# communicator_v2p3.net
KiCad netlist of a schematic drawn in EAGLE
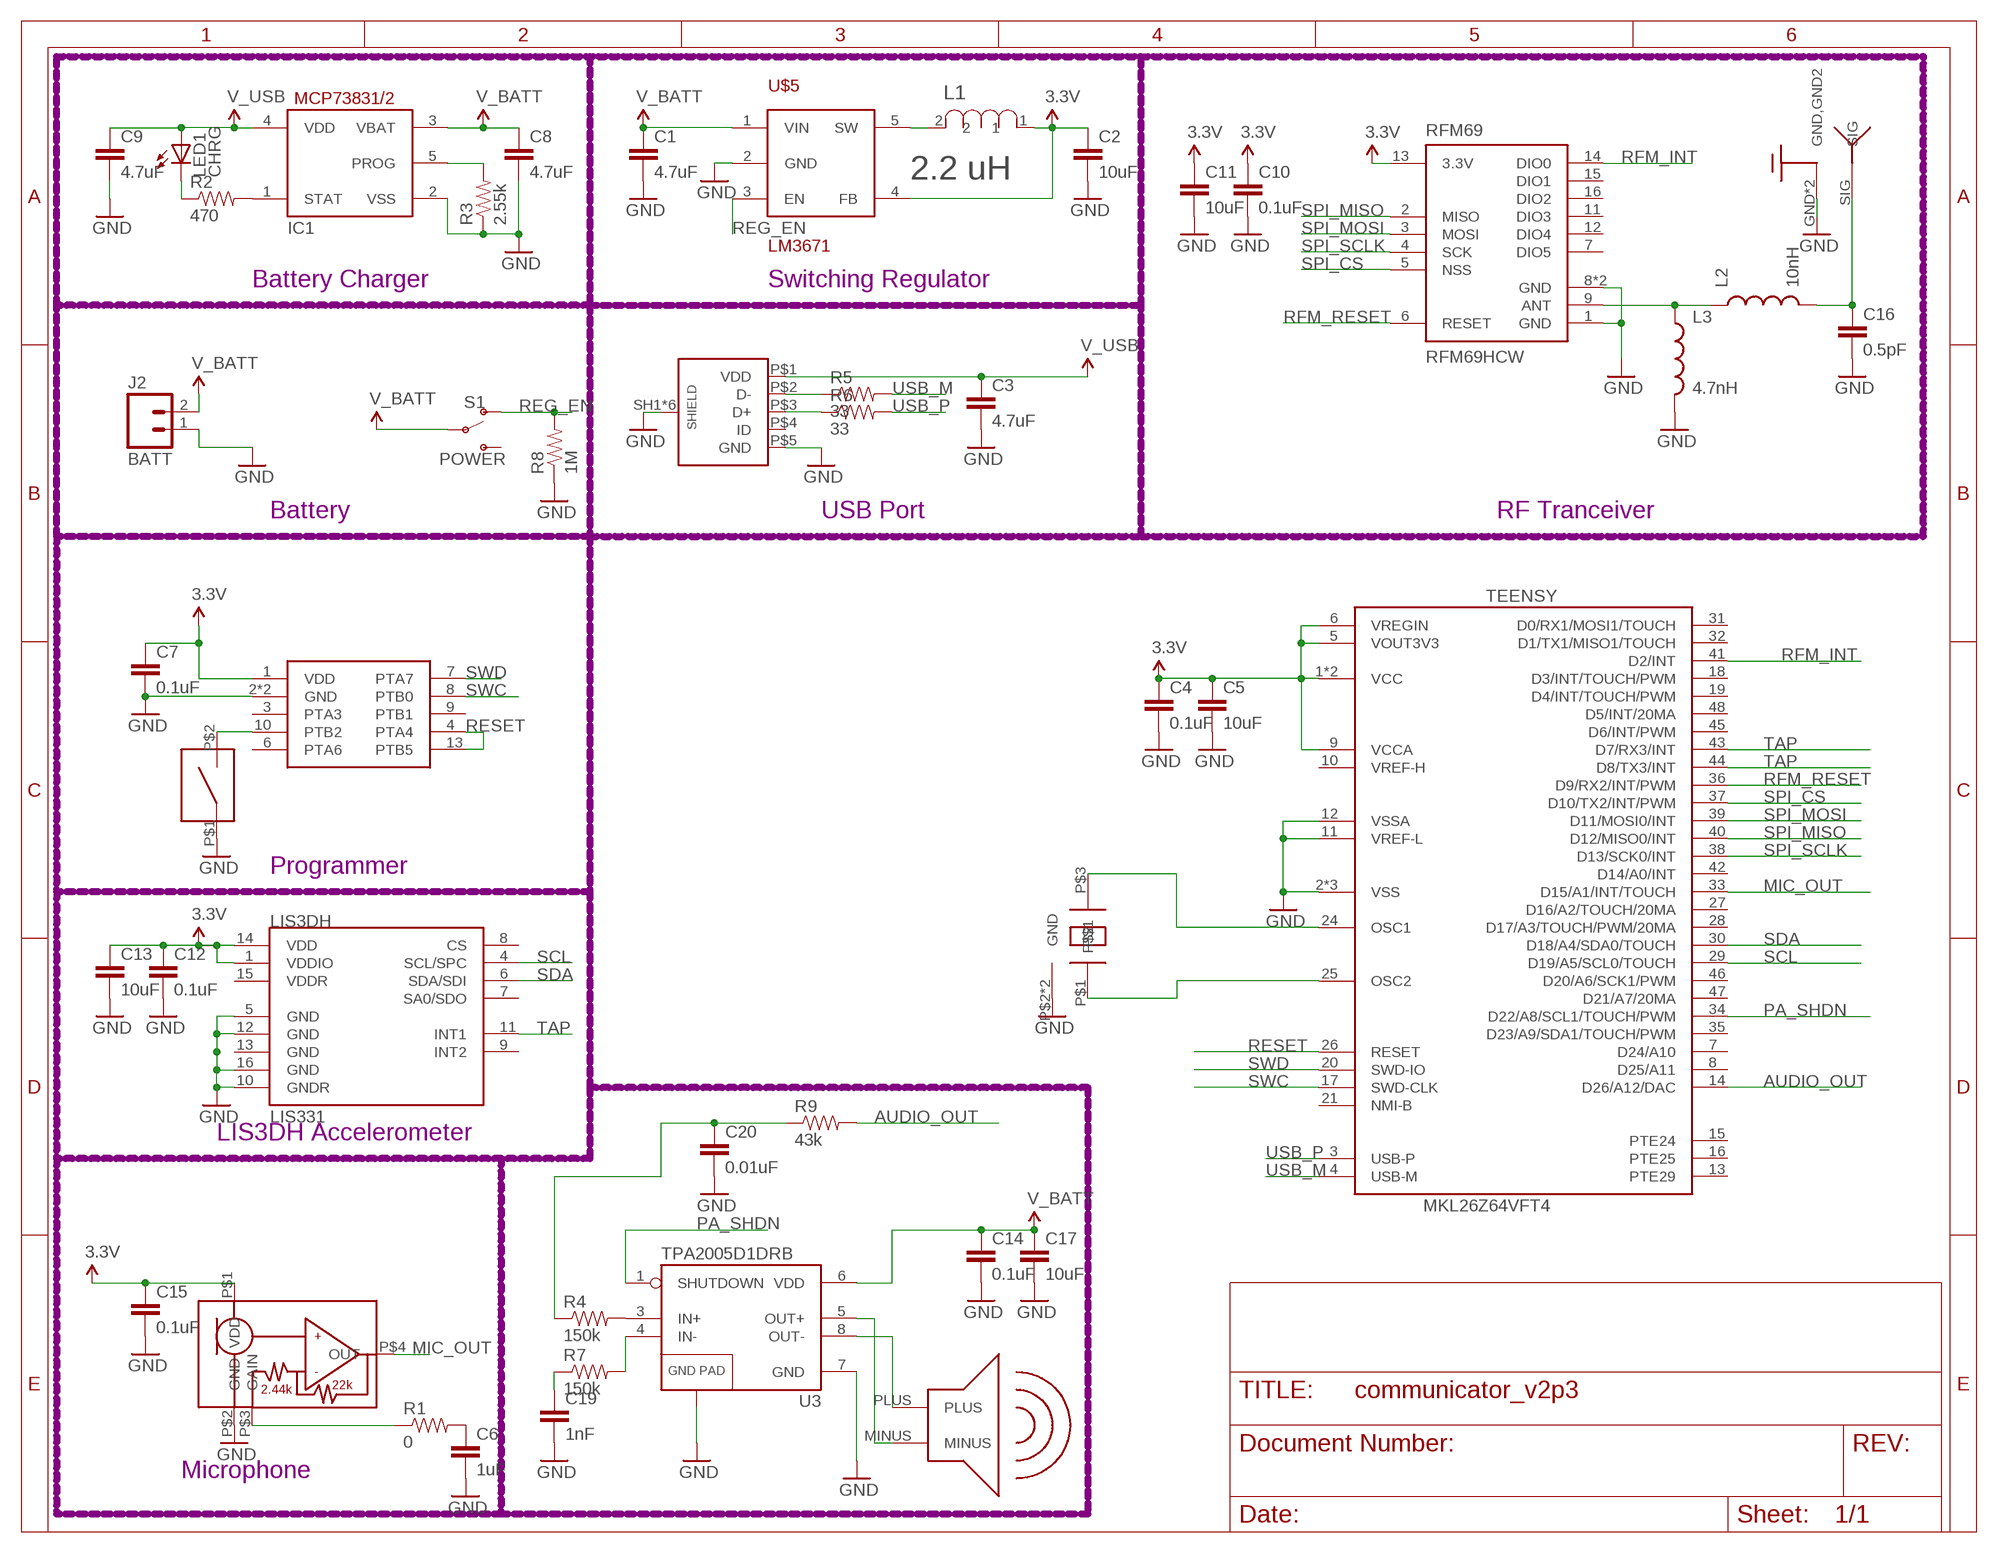
[diagram p0: schematic, sheet 1]

(export (version "E")
  (design (tool "Eeschema 10.0.6"))
  (components
    (comp (ref "3X3MM1")
      (value "CURRENT_BOOTLOADER3X3MM")
      (footprint "eagle-import:QFN50P300X300X100-17N")
      (libsource (lib "eagle-import") (part "CURRENT_BOOTLOADER3X3MM"))
    )
    (comp (ref "C1")
      (value "4.7uF")
      (footprint "eagle-import:0603-CAP")
      (libsource (lib "eagle-import") (part "0.1UF-25V(+80/-20%)(0603)"))
    )
    (comp (ref "C2")
      (value "10uF")
      (footprint "eagle-import:0603-CAP")
      (libsource (lib "eagle-import") (part "2.2UF-10V-20%(0603)"))
    )
    (comp (ref "C3")
      (value "4.7uF")
      (footprint "eagle-import:0603-CAP")
      (libsource (lib "eagle-import") (part "2.2UF-10V-20%(0603)"))
    )
    (comp (ref "C4")
      (value "0.1uF")
      (footprint "eagle-import:0603-CAP")
      (libsource (lib "eagle-import") (part "0.1UF-25V(+80/-20%)(0603)"))
    )
    (comp (ref "C5")
      (value "10uF")
      (footprint "eagle-import:0603-CAP")
      (libsource (lib "eagle-import") (part "10UF-6.3V-20%(0603)"))
    )
    (comp (ref "C6")
      (value "1uF")
      (footprint "eagle-import:0603-CAP")
      (libsource (lib "eagle-import") (part "0.1UF-25V(+80/-20%)(0603)"))
    )
    (comp (ref "C7")
      (value "0.1uF")
      (footprint "eagle-import:0603-CAP")
      (libsource (lib "eagle-import") (part "0.1UF-25V(+80/-20%)(0603)"))
    )
    (comp (ref "C8")
      (value "4.7uF")
      (footprint "eagle-import:0603-CAP")
      (libsource (lib "eagle-import") (part "4.7UF-6.3V-10%(0603)0603"))
    )
    (comp (ref "C9")
      (value "4.7uF")
      (footprint "eagle-import:0603-CAP")
      (libsource (lib "eagle-import") (part "4.7UF-6.3V-10%(0603)0603"))
    )
    (comp (ref "C10")
      (value "0.1uF")
      (footprint "eagle-import:0603-CAP")
      (libsource (lib "eagle-import") (part "0.1UF-25V(+80/-20%)(0603)"))
    )
    (comp (ref "C11")
      (value "10uF")
      (footprint "eagle-import:0603-CAP")
      (libsource (lib "eagle-import") (part "10UF-6.3V-20%(0603)"))
    )
    (comp (ref "C12")
      (value "0.1uF")
      (footprint "eagle-import:0603-CAP")
      (libsource (lib "eagle-import") (part "0.1UF-25V(+80/-20%)(0603)"))
    )
    (comp (ref "C13")
      (value "10uF")
      (footprint "eagle-import:0603-CAP")
      (libsource (lib "eagle-import") (part "10UF-6.3V-20%(0603)"))
    )
    (comp (ref "C14")
      (value "0.1uF")
      (footprint "eagle-import:0603-CAP")
      (libsource (lib "eagle-import") (part "0.1UF-25V(+80/-20%)(0603)"))
    )
    (comp (ref "C15")
      (value "0.1uF")
      (footprint "eagle-import:0603-CAP")
      (libsource (lib "eagle-import") (part "0.1UF-25V(+80/-20%)(0603)"))
    )
    (comp (ref "C16")
      (value "0.5pF")
      (footprint "eagle-import:0603-CAP")
      (libsource (lib "eagle-import") (part "0.75PF-50V(-/+.25PF)(0603)"))
    )
    (comp (ref "C17")
      (value "10uF")
      (footprint "eagle-import:0603-CAP")
      (libsource (lib "eagle-import") (part "10UF-6.3V-20%(0603)"))
    )
    (comp (ref "C19")
      (value "1nF")
      (footprint "eagle-import:0603-CAP")
      (libsource (lib "eagle-import") (part "0.1UF-25V(+80/-20%)(0603)"))
    )
    (comp (ref "C20")
      (value "0.01uF")
      (footprint "eagle-import:0603-CAP")
      (libsource (lib "eagle-import") (part "0.1UF-25V(+80/-20%)(0603)"))
    )
    (comp (ref "IC1")
      (value "MCP73831/OT")
      (footprint "eagle-import:SOT23-5L")
      (libsource (lib "eagle-import") (part "MCP73831/OT"))
    )
    (comp (ref "J2")
      (value "BATT")
      (footprint "eagle-import:1X02")
      (libsource (lib "eagle-import") (part "M02PTH"))
    )
    (comp (ref "L1")
      (value "2.2 uH")
      (footprint "eagle-import:INDC3225X22N")
      (fields (field (name "MPN") "PM1210-2R2J-RC") (field (name "TOLERANCE") "±5 %"))
      (libsource (lib "eagle-import") (part "PM1210-2R2J-RC"))
    )
    (comp (ref "L2")
      (value "10nH")
      (footprint "eagle-import:0603")
      (libsource (lib "eagle-import") (part "INDUCTOR0603"))
    )
    (comp (ref "L3")
      (value "4.7nH")
      (footprint "eagle-import:0603")
      (libsource (lib "eagle-import") (part "INDUCTOR0603"))
    )
    (comp (ref "LED1")
      (value "CHRG")
      (footprint "eagle-import:CHIPLED_0805")
      (libsource (lib "eagle-import") (part "LEDCHIPLED_0805"))
    )
    (comp (ref "LIS3DH")
      (value "LIS331")
      (footprint "eagle-import:LGA16-3MM")
      (libsource (lib "eagle-import") (part "LIS331"))
    )
    (comp (ref "R1")
      (value "0")
      (footprint "eagle-import:0603-RES")
      (libsource (lib "eagle-import") (part "33OHM1/10W1%(0603)"))
    )
    (comp (ref "R2")
      (value "470")
      (footprint "eagle-import:0603-RES")
      (libsource (lib "eagle-import") (part "470OHM1/10W1%(0603)"))
    )
    (comp (ref "R3")
      (value "2.55k")
      (footprint "eagle-import:0603-RES")
      (libsource (lib "eagle-import") (part "2.55KOHM-1/10W-1%(0603)"))
    )
    (comp (ref "R4")
      (value "150k")
      (footprint "eagle-import:0603-RES")
      (libsource (lib "eagle-import") (part "33OHM1/10W1%(0603)"))
    )
    (comp (ref "R5")
      (value "33")
      (footprint "eagle-import:0603-RES")
      (libsource (lib "eagle-import") (part "33OHM1/10W1%(0603)"))
    )
    (comp (ref "R6")
      (value "33")
      (footprint "eagle-import:0603-RES")
      (libsource (lib "eagle-import") (part "33OHM1/10W1%(0603)"))
    )
    (comp (ref "R7")
      (value "150k")
      (footprint "eagle-import:0603-RES")
      (libsource (lib "eagle-import") (part "33OHM1/10W1%(0603)"))
    )
    (comp (ref "R8")
      (value "1M")
      (footprint "eagle-import:0603-RES")
      (libsource (lib "eagle-import") (part "2.55KOHM-1/10W-1%(0603)"))
    )
    (comp (ref "R9")
      (value "43k")
      (footprint "eagle-import:0603-RES")
      (libsource (lib "eagle-import") (part "33OHM1/10W1%(0603)"))
    )
    (comp (ref "RFM69")
      (value "RFM69HCW")
      (footprint "eagle-import:RFM69HCW-XXXS2")
      (libsource (lib "eagle-import") (part "RFM69HCW"))
    )
    (comp (ref "S1")
      (value "POWER")
      (footprint "eagle-import:SWITCH_SPST_SMD_A")
      (libsource (lib "eagle-import") (part "SWITCH-SPDT-SMD-RIGHT-ANGLE"))
    )
    (comp (ref "TEENSY")
      (value "MKL26Z64VFT4")
      (footprint "eagle-import:QFN50P700X700X100-49N")
      (libsource (lib "eagle-import") (part "MKL26Z64VFT4"))
    )
    (comp (ref "U$1")
      (value "ANTENNA_915MHZ")
      (footprint "eagle-import:ANTENNA_915MHZ")
      (libsource (lib "eagle-import") (part "ANTENNA_915MHZ"))
    )
    (comp (ref "U$2")
      (value "MICROPHONE")
      (footprint "eagle-import:SPU0414HR5H-SB")
      (libsource (lib "eagle-import") (part "MICROPHONE"))
    )
    (comp (ref "U$3")
      (value "SPEAKER")
      (footprint "eagle-import:PSR1511N08S3K")
      (libsource (lib "eagle-import") (part "SPEAKER"))
    )
    (comp (ref "U$4")
      (value "KXT131LHS")
      (footprint "eagle-import:KXT131LHS")
      (libsource (lib "eagle-import") (part "KXT131LHS"))
    )
    (comp (ref "U$5")
      (value "LM3671")
      (footprint "eagle-import:SOT23-5")
      (libsource (lib "eagle-import") (part "LM3671"))
    )
    (comp (ref "U$8")
      (value "MICRO_USB_B")
      (footprint "eagle-import:MICRO_USB_B")
      (libsource (lib "eagle-import") (part "MICRO_USB_B"))
    )
    (comp (ref "U$9")
      (value "TSX-3225")
      (footprint "eagle-import:TSX-3225")
      (libsource (lib "eagle-import") (part "TSX-3225"))
    )
    (comp (ref "U3")
      (value "TPA2005D1DRB")
      (footprint "eagle-import:QFN-8_PAD")
      (libsource (lib "eagle-import") (part "TPA2005D1DRB"))
    )
  )
  (nets
    (net (code "1") (name "/AUDIO_OUT") (class "Default")
      (node (ref "R9") (pin "2") (pinfunction "2_2") (pintype "passive"))
      (node (ref "TEENSY") (pin "14") (pinfunction "D26/A12/DAC_14") (pintype "bidirectional"))
    )
    (net (code "2") (name "/MIC_OUT") (class "Default")
      (node (ref "TEENSY") (pin "33") (pinfunction "D15/A1/INT/TOUCH_33") (pintype "bidirectional"))
      (node (ref "U$2") (pin "P$4") (pinfunction "OUT_P$4") (pintype "bidirectional"))
    )
    (net (code "3") (name "/PA_SHDN") (class "Default")
      (node (ref "TEENSY") (pin "34") (pinfunction "D22/A8/SCL1/TOUCH/PWM_34") (pintype "bidirectional"))
      (node (ref "U3") (pin "1") (pinfunction "SHUTDOWN_1") (pintype "input"))
    )
    (net (code "4") (name "/REG_EN") (class "Default")
      (node (ref "R8") (pin "2") (pinfunction "2_2") (pintype "passive"))
      (node (ref "S1") (pin "1") (pinfunction "O_1") (pintype "passive"))
      (node (ref "U$5") (pin "3") (pinfunction "EN_3") (pintype "bidirectional"))
    )
    (net (code "5") (name "/RESET") (class "Default")
      (node (ref "3X3MM1") (pin "13") (pinfunction "PTB5_13") (pintype "bidirectional"))
      (node (ref "3X3MM1") (pin "4") (pinfunction "PTA4_4") (pintype "bidirectional"))
      (node (ref "TEENSY") (pin "26") (pinfunction "RESET_26") (pintype "bidirectional"))
    )
    (net (code "6") (name "/RFM_INT") (class "Default")
      (node (ref "RFM69") (pin "14") (pinfunction "DIO0_14") (pintype "bidirectional"))
      (node (ref "TEENSY") (pin "41") (pinfunction "D2/INT_41") (pintype "bidirectional"))
    )
    (net (code "7") (name "/RFM_RESET") (class "Default")
      (node (ref "RFM69") (pin "6") (pinfunction "RESET_6") (pintype "input"))
      (node (ref "TEENSY") (pin "36") (pinfunction "D9/RX2/INT/PWM_36") (pintype "bidirectional"))
    )
    (net (code "8") (name "/SCL") (class "Default")
      (node (ref "LIS3DH") (pin "4") (pinfunction "SCL/SPC_4") (pintype "bidirectional"))
      (node (ref "TEENSY") (pin "29") (pinfunction "D19/A5/SCL0/TOUCH_29") (pintype "bidirectional"))
    )
    (net (code "9") (name "/SDA") (class "Default")
      (node (ref "LIS3DH") (pin "6") (pinfunction "SDA/SDI_6") (pintype "bidirectional"))
      (node (ref "TEENSY") (pin "30") (pinfunction "D18/A4/SDA0/TOUCH_30") (pintype "bidirectional"))
    )
    (net (code "10") (name "/SPI_CS") (class "Default")
      (node (ref "RFM69") (pin "5") (pinfunction "NSS_5") (pintype "input"))
      (node (ref "TEENSY") (pin "37") (pinfunction "D10/TX2/INT/PWM_37") (pintype "bidirectional"))
    )
    (net (code "11") (name "/SPI_MISO") (class "Default")
      (node (ref "RFM69") (pin "2") (pinfunction "MISO_2") (pintype "bidirectional"))
      (node (ref "TEENSY") (pin "40") (pinfunction "D12/MISO0/INT_40") (pintype "bidirectional"))
    )
    (net (code "12") (name "/SPI_MOSI") (class "Default")
      (node (ref "RFM69") (pin "3") (pinfunction "MOSI_3") (pintype "input"))
      (node (ref "TEENSY") (pin "39") (pinfunction "D11/MOSI0/INT_39") (pintype "bidirectional"))
    )
    (net (code "13") (name "/SPI_SCLK") (class "Default")
      (node (ref "RFM69") (pin "4") (pinfunction "SCK_4") (pintype "input"))
      (node (ref "TEENSY") (pin "38") (pinfunction "D13/SCK0/INT_38") (pintype "bidirectional"))
    )
    (net (code "14") (name "/SWC") (class "Default")
      (node (ref "3X3MM1") (pin "8") (pinfunction "PTB0_8") (pintype "bidirectional"))
      (node (ref "TEENSY") (pin "17") (pinfunction "SWD-CLK_17") (pintype "bidirectional"))
    )
    (net (code "15") (name "/SWD") (class "Default")
      (node (ref "3X3MM1") (pin "7") (pinfunction "PTA7_7") (pintype "bidirectional"))
      (node (ref "TEENSY") (pin "20") (pinfunction "SWD-IO_20") (pintype "bidirectional"))
    )
    (net (code "16") (name "/TAP") (class "Default")
      (node (ref "LIS3DH") (pin "11") (pinfunction "INT1_11") (pintype "bidirectional"))
      (node (ref "TEENSY") (pin "43") (pinfunction "D7/RX3/INT_43") (pintype "bidirectional"))
      (node (ref "TEENSY") (pin "44") (pinfunction "D8/TX3/INT_44") (pintype "bidirectional"))
    )
    (net (code "17") (name "/USB_M") (class "Default")
      (node (ref "R5") (pin "2") (pinfunction "2_2") (pintype "passive"))
      (node (ref "TEENSY") (pin "4") (pinfunction "USB-M_4") (pintype "bidirectional"))
    )
    (net (code "18") (name "/USB_P") (class "Default")
      (node (ref "R6") (pin "2") (pinfunction "2_2") (pintype "passive"))
      (node (ref "TEENSY") (pin "3") (pinfunction "USB-P_3") (pintype "bidirectional"))
    )
    (net (code "19") (name "3.3V") (class "Default")
      (node (ref "3X3MM1") (pin "1") (pinfunction "VDD_1") (pintype "bidirectional"))
      (node (ref "C10") (pin "1") (pinfunction "1_1") (pintype "passive"))
      (node (ref "C11") (pin "1") (pinfunction "1_1") (pintype "passive"))
      (node (ref "C12") (pin "1") (pinfunction "1_1") (pintype "passive"))
      (node (ref "C13") (pin "1") (pinfunction "1_1") (pintype "passive"))
      (node (ref "C15") (pin "1") (pinfunction "1_1") (pintype "passive"))
      (node (ref "C2") (pin "1") (pinfunction "1_1") (pintype "passive"))
      (node (ref "C4") (pin "1") (pinfunction "1_1") (pintype "passive"))
      (node (ref "C5") (pin "1") (pinfunction "1_1") (pintype "passive"))
      (node (ref "C7") (pin "1") (pinfunction "1_1") (pintype "passive"))
      (node (ref "L1") (pin "1") (pinfunction "1_1") (pintype "passive"))
      (node (ref "LIS3DH") (pin "1") (pinfunction "VDDIO_1") (pintype "bidirectional"))
      (node (ref "LIS3DH") (pin "14") (pinfunction "VDD_14") (pintype "bidirectional"))
      (node (ref "RFM69") (pin "13") (pinfunction "3.3V_13") (pintype "power_in"))
      (node (ref "TEENSY") (pin "1") (pinfunction "VCC_1") (pintype "bidirectional"))
      (node (ref "TEENSY") (pin "22") (pinfunction "VCC_22") (pintype "bidirectional"))
      (node (ref "TEENSY") (pin "5") (pinfunction "VOUT3V3_5") (pintype "bidirectional"))
      (node (ref "TEENSY") (pin "6") (pinfunction "VREGIN_6") (pintype "bidirectional"))
      (node (ref "TEENSY") (pin "9") (pinfunction "VCCA_9") (pintype "bidirectional"))
      (node (ref "U$2") (pin "P$1") (pinfunction "VDD_P$1") (pintype "bidirectional"))
      (node (ref "U$5") (pin "4") (pinfunction "FB_4") (pintype "bidirectional"))
    )
    (net (code "20") (name "GND") (class "Default")
      (node (ref "3X3MM1") (pin "17") (pinfunction "GND_17") (pintype "bidirectional"))
      (node (ref "3X3MM1") (pin "2") (pinfunction "GND_2") (pintype "bidirectional"))
      (node (ref "C1") (pin "2") (pinfunction "2_2") (pintype "passive"))
      (node (ref "C10") (pin "2") (pinfunction "2_2") (pintype "passive"))
      (node (ref "C11") (pin "2") (pinfunction "2_2") (pintype "passive"))
      (node (ref "C12") (pin "2") (pinfunction "2_2") (pintype "passive"))
      (node (ref "C13") (pin "2") (pinfunction "2_2") (pintype "passive"))
      (node (ref "C14") (pin "2") (pinfunction "2_2") (pintype "passive"))
      (node (ref "C15") (pin "2") (pinfunction "2_2") (pintype "passive"))
      (node (ref "C16") (pin "2") (pinfunction "2_2") (pintype "passive"))
      (node (ref "C17") (pin "2") (pinfunction "2_2") (pintype "passive"))
      (node (ref "C19") (pin "2") (pinfunction "2_2") (pintype "passive"))
      (node (ref "C2") (pin "2") (pinfunction "2_2") (pintype "passive"))
      (node (ref "C20") (pin "2") (pinfunction "2_2") (pintype "passive"))
      (node (ref "C3") (pin "2") (pinfunction "2_2") (pintype "passive"))
      (node (ref "C4") (pin "2") (pinfunction "2_2") (pintype "passive"))
      (node (ref "C5") (pin "2") (pinfunction "2_2") (pintype "passive"))
      (node (ref "C6") (pin "2") (pinfunction "2_2") (pintype "passive"))
      (node (ref "C7") (pin "2") (pinfunction "2_2") (pintype "passive"))
      (node (ref "C8") (pin "2") (pinfunction "2_2") (pintype "passive"))
      (node (ref "C9") (pin "2") (pinfunction "2_2") (pintype "passive"))
      (node (ref "IC1") (pin "2") (pinfunction "VSS_2") (pintype "power_in"))
      (node (ref "J2") (pin "1") (pinfunction "1_1") (pintype "passive"))
      (node (ref "L3") (pin "2") (pinfunction "2_2") (pintype "passive"))
      (node (ref "LIS3DH") (pin "10") (pinfunction "GNDR_10") (pintype "bidirectional"))
      (node (ref "LIS3DH") (pin "12") (pinfunction "GND_12") (pintype "bidirectional"))
      (node (ref "LIS3DH") (pin "16") (pinfunction "GND_16") (pintype "bidirectional"))
      (node (ref "LIS3DH") (pin "5") (pinfunction "GND_5") (pintype "bidirectional"))
      (node (ref "R3") (pin "1") (pinfunction "1_1") (pintype "passive"))
      (node (ref "R8") (pin "1") (pinfunction "1_1") (pintype "passive"))
      (node (ref "RFM69") (pin "1") (pinfunction "GND_1") (pintype "power_in"))
      (node (ref "RFM69") (pin "10") (pinfunction "GND_10") (pintype "power_in"))
      (node (ref "RFM69") (pin "8") (pinfunction "GND_8") (pintype "power_in"))
      (node (ref "TEENSY") (pin "11") (pinfunction "VREF-L_11") (pintype "bidirectional"))
      (node (ref "TEENSY") (pin "12") (pinfunction "VSSA_12") (pintype "bidirectional"))
      (node (ref "TEENSY") (pin "2") (pinfunction "VSS_2") (pintype "bidirectional"))
      (node (ref "TEENSY") (pin "23") (pinfunction "VSS_23") (pintype "bidirectional"))
      (node (ref "TEENSY") (pin "49") (pinfunction "VSS_49") (pintype "bidirectional"))
      (node (ref "U$1") (pin "GND") (pinfunction "GND,GND2_GND") (pintype "bidirectional"))
      (node (ref "U$1") (pin "GND2") (pinfunction "GND,GND2_GND2") (pintype "bidirectional"))
      (node (ref "U$2") (pin "P$2") (pinfunction "GND_P$2") (pintype "bidirectional"))
      (node (ref "U$4") (pin "P$1") (pinfunction "P$1_P$1") (pintype "bidirectional"))
      (node (ref "U$5") (pin "2") (pinfunction "GND_2") (pintype "bidirectional"))
      (node (ref "U$8") (pin "P$5") (pinfunction "GND_P$5") (pintype "bidirectional"))
      (node (ref "U$8") (pin "SH1") (pinfunction "SHIELD_SH1") (pintype "bidirectional"))
      (node (ref "U$8") (pin "SH2") (pinfunction "SHIELD_SH2") (pintype "bidirectional"))
      (node (ref "U$8") (pin "SH3") (pinfunction "SHIELD_SH3") (pintype "bidirectional"))
      (node (ref "U$8") (pin "SH4") (pinfunction "SHIELD_SH4") (pintype "bidirectional"))
      (node (ref "U$8") (pin "SH5") (pinfunction "SHIELD_SH5") (pintype "bidirectional"))
      (node (ref "U$8") (pin "SH6") (pinfunction "SHIELD_SH6") (pintype "bidirectional"))
      (node (ref "U$9") (pin "P$2") (pinfunction "GND_P$2") (pintype "bidirectional"))
      (node (ref "U$9") (pin "P$4") (pinfunction "GND_P$4") (pintype "bidirectional"))
      (node (ref "U3") (pin "10") (pinfunction "GND_10") (pintype "power_in"))
      (node (ref "U3") (pin "11") (pinfunction "GND_11") (pintype "power_in"))
      (node (ref "U3") (pin "12") (pinfunction "GND_12") (pintype "power_in"))
      (node (ref "U3") (pin "13") (pinfunction "GND_13") (pintype "power_in"))
      (node (ref "U3") (pin "7") (pinfunction "GND_7") (pintype "power_in"))
      (node (ref "U3") (pin "9") (pinfunction "GND_9") (pintype "power_in"))
    )
    (net (code "21") (name "Net-(3X3MM1-PTB2)") (class "Default")
      (node (ref "3X3MM1") (pin "10") (pinfunction "PTB2_10") (pintype "bidirectional"))
      (node (ref "U$4") (pin "P$2") (pinfunction "P$2_P$2") (pintype "bidirectional"))
    )
    (net (code "22") (name "Net-(C6-Pad1)") (class "Default")
      (node (ref "C6") (pin "1") (pinfunction "1_1") (pintype "passive"))
      (node (ref "R1") (pin "2") (pinfunction "2_2") (pintype "passive"))
    )
    (net (code "23") (name "Net-(C16-Pad1)") (class "Default")
      (node (ref "C16") (pin "1") (pinfunction "1_1") (pintype "passive"))
      (node (ref "L2") (pin "2") (pinfunction "2_2") (pintype "passive"))
      (node (ref "U$1") (pin "SIG") (pinfunction "SIG_SIG") (pintype "bidirectional"))
    )
    (net (code "24") (name "Net-(C19-Pad1)") (class "Default")
      (node (ref "C19") (pin "1") (pinfunction "1_1") (pintype "passive"))
      (node (ref "R7") (pin "1") (pinfunction "1_1") (pintype "passive"))
    )
    (net (code "25") (name "Net-(C20-Pad1)") (class "Default")
      (node (ref "C20") (pin "1") (pinfunction "1_1") (pintype "passive"))
      (node (ref "R4") (pin "1") (pinfunction "1_1") (pintype "passive"))
      (node (ref "R9") (pin "1") (pinfunction "1_1") (pintype "passive"))
    )
    (net (code "26") (name "Net-(IC1-PROG)") (class "Default")
      (node (ref "IC1") (pin "5") (pinfunction "PROG_5") (pintype "input"))
      (node (ref "R3") (pin "2") (pinfunction "2_2") (pintype "passive"))
    )
    (net (code "27") (name "Net-(IC1-STAT)") (class "Default")
      (node (ref "IC1") (pin "1") (pinfunction "STAT_1") (pintype "output"))
      (node (ref "R2") (pin "2") (pinfunction "2_2") (pintype "passive"))
    )
    (net (code "28") (name "Net-(LED1-PadC)") (class "Default")
      (node (ref "LED1") (pin "C") (pinfunction "C_C") (pintype "passive"))
      (node (ref "R2") (pin "1") (pinfunction "1_1") (pintype "passive"))
    )
    (net (code "29") (name "Net-(RFM69-ANT)") (class "Default")
      (node (ref "L2") (pin "1") (pinfunction "1_1") (pintype "passive"))
      (node (ref "L3") (pin "1") (pinfunction "1_1") (pintype "passive"))
      (node (ref "RFM69") (pin "9") (pinfunction "ANT_9") (pintype "passive"))
    )
    (net (code "30") (name "Net-(TEENSY-OSC1)") (class "Default")
      (node (ref "TEENSY") (pin "24") (pinfunction "OSC1_24") (pintype "bidirectional"))
      (node (ref "U$9") (pin "P$3") (pinfunction "P$2_P$3") (pintype "bidirectional"))
    )
    (net (code "31") (name "Net-(TEENSY-OSC2)") (class "Default")
      (node (ref "TEENSY") (pin "25") (pinfunction "OSC2_25") (pintype "bidirectional"))
      (node (ref "U$9") (pin "P$1") (pinfunction "P$1_P$1") (pintype "bidirectional"))
    )
    (net (code "32") (name "Net-(U$2-GAIN)") (class "Default")
      (node (ref "R1") (pin "1") (pinfunction "1_1") (pintype "passive"))
      (node (ref "U$2") (pin "P$3") (pinfunction "GAIN_P$3") (pintype "bidirectional"))
    )
    (net (code "33") (name "Net-(U$5-SW)") (class "Default")
      (node (ref "L1") (pin "2") (pinfunction "2_2") (pintype "passive"))
      (node (ref "U$5") (pin "5") (pinfunction "SW_5") (pintype "bidirectional"))
    )
    (net (code "34") (name "Net-(U$8-D+)") (class "Default")
      (node (ref "R6") (pin "1") (pinfunction "1_1") (pintype "passive"))
      (node (ref "U$8") (pin "P$3") (pinfunction "D+_P$3") (pintype "bidirectional"))
    )
    (net (code "35") (name "Net-(U$8-D-)") (class "Default")
      (node (ref "R5") (pin "1") (pinfunction "1_1") (pintype "passive"))
      (node (ref "U$8") (pin "P$2") (pinfunction "D-_P$2") (pintype "bidirectional"))
    )
    (net (code "36") (name "Net-(U3-IN+)") (class "Default")
      (node (ref "R4") (pin "2") (pinfunction "2_2") (pintype "passive"))
      (node (ref "U3") (pin "3") (pinfunction "IN+_3") (pintype "bidirectional"))
    )
    (net (code "37") (name "Net-(U3-IN-)") (class "Default")
      (node (ref "R7") (pin "2") (pinfunction "2_2") (pintype "passive"))
      (node (ref "U3") (pin "4") (pinfunction "IN-_4") (pintype "bidirectional"))
    )
    (net (code "38") (name "Net-(U3-OUT+)") (class "Default")
      (node (ref "U$3") (pin "MINUS") (pinfunction "MINUS_MINUS") (pintype "bidirectional"))
      (node (ref "U3") (pin "5") (pinfunction "OUT+_5") (pintype "bidirectional"))
    )
    (net (code "39") (name "Net-(U3-OUT-)") (class "Default")
      (node (ref "U$3") (pin "PLUS") (pinfunction "PLUS_PLUS") (pintype "bidirectional"))
      (node (ref "U3") (pin "8") (pinfunction "OUT-_8") (pintype "bidirectional"))
    )
    (net (code "40") (name "V_BATT") (class "Default")
      (node (ref "C1") (pin "1") (pinfunction "1_1") (pintype "passive"))
      (node (ref "C14") (pin "1") (pinfunction "1_1") (pintype "passive"))
      (node (ref "C17") (pin "1") (pinfunction "1_1") (pintype "passive"))
      (node (ref "C8") (pin "1") (pinfunction "1_1") (pintype "passive"))
      (node (ref "IC1") (pin "3") (pinfunction "VBAT_3") (pintype "bidirectional"))
      (node (ref "J2") (pin "2") (pinfunction "2_2") (pintype "passive"))
      (node (ref "S1") (pin "2") (pinfunction "P_2") (pintype "passive"))
      (node (ref "U$5") (pin "1") (pinfunction "VIN_1") (pintype "bidirectional"))
      (node (ref "U3") (pin "6") (pinfunction "VDD_6") (pintype "power_in"))
    )
    (net (code "41") (name "V_USB") (class "Default")
      (node (ref "C3") (pin "1") (pinfunction "1_1") (pintype "passive"))
      (node (ref "C9") (pin "1") (pinfunction "1_1") (pintype "passive"))
      (node (ref "IC1") (pin "4") (pinfunction "VDD_4") (pintype "power_in"))
      (node (ref "LED1") (pin "A") (pinfunction "A_A") (pintype "passive"))
      (node (ref "U$8") (pin "P$1") (pinfunction "VDD_P$1") (pintype "bidirectional"))
    )
    (net (code "42") (name "unconnected-(3X3MM1-PTA3-Pad3)") (class "Default")
      (node (ref "3X3MM1") (pin "3") (pinfunction "PTA3_3") (pintype "bidirectional"))
    )
    (net (code "43") (name "unconnected-(3X3MM1-PTA6-Pad6)") (class "Default")
      (node (ref "3X3MM1") (pin "6") (pinfunction "PTA6_6") (pintype "bidirectional"))
    )
    (net (code "44") (name "unconnected-(3X3MM1-PTB1-Pad9)") (class "Default")
      (node (ref "3X3MM1") (pin "9") (pinfunction "PTB1_9") (pintype "bidirectional"))
    )
    (net (code "45") (name "unconnected-(LIS3DH-CS-Pad8)") (class "Default")
      (node (ref "LIS3DH") (pin "8") (pinfunction "CS_8") (pintype "bidirectional"))
    )
    (net (code "46") (name "unconnected-(LIS3DH-GND-Pad13)") (class "Default")
      (node (ref "LIS3DH") (pin "13") (pinfunction "GND_13") (pintype "bidirectional"))
    )
    (net (code "47") (name "unconnected-(LIS3DH-INT2-Pad9)") (class "Default")
      (node (ref "LIS3DH") (pin "9") (pinfunction "INT2_9") (pintype "bidirectional"))
    )
    (net (code "48") (name "unconnected-(LIS3DH-SA0{slash}SDO-Pad7)") (class "Default")
      (node (ref "LIS3DH") (pin "7") (pinfunction "SA0/SDO_7") (pintype "bidirectional"))
    )
    (net (code "49") (name "unconnected-(LIS3DH-VDDR-Pad15)") (class "Default")
      (node (ref "LIS3DH") (pin "15") (pinfunction "VDDR_15") (pintype "bidirectional"))
    )
    (net (code "50") (name "unconnected-(RFM69-DIO1-Pad15)") (class "Default")
      (node (ref "RFM69") (pin "15") (pinfunction "DIO1_15") (pintype "bidirectional"))
    )
    (net (code "51") (name "unconnected-(RFM69-DIO2-Pad16)") (class "Default")
      (node (ref "RFM69") (pin "16") (pinfunction "DIO2_16") (pintype "bidirectional"))
    )
    (net (code "52") (name "unconnected-(RFM69-DIO3-Pad11)") (class "Default")
      (node (ref "RFM69") (pin "11") (pinfunction "DIO3_11") (pintype "bidirectional"))
    )
    (net (code "53") (name "unconnected-(RFM69-DIO4-Pad12)") (class "Default")
      (node (ref "RFM69") (pin "12") (pinfunction "DIO4_12") (pintype "bidirectional"))
    )
    (net (code "54") (name "unconnected-(RFM69-DIO5-Pad7)") (class "Default")
      (node (ref "RFM69") (pin "7") (pinfunction "DIO5_7") (pintype "bidirectional"))
    )
    (net (code "55") (name "unconnected-(S1-S-Pad3)") (class "Default")
      (node (ref "S1") (pin "3") (pinfunction "S_3") (pintype "passive"))
    )
    (net (code "56") (name "unconnected-(TEENSY-D0{slash}RX1{slash}MOSI1{slash}TOUCH-Pad31)") (class "Default")
      (node (ref "TEENSY") (pin "31") (pinfunction "D0/RX1/MOSI1/TOUCH_31") (pintype "bidirectional"))
    )
    (net (code "57") (name "unconnected-(TEENSY-D1{slash}TX1{slash}MISO1{slash}TOUCH-Pad32)") (class "Default")
      (node (ref "TEENSY") (pin "32") (pinfunction "D1/TX1/MISO1/TOUCH_32") (pintype "bidirectional"))
    )
    (net (code "58") (name "unconnected-(TEENSY-D3{slash}INT{slash}TOUCH{slash}PWM-Pad18)") (class "Default")
      (node (ref "TEENSY") (pin "18") (pinfunction "D3/INT/TOUCH/PWM_18") (pintype "bidirectional"))
    )
    (net (code "59") (name "unconnected-(TEENSY-D4{slash}INT{slash}TOUCH{slash}PWM-Pad19)") (class "Default")
      (node (ref "TEENSY") (pin "19") (pinfunction "D4/INT/TOUCH/PWM_19") (pintype "bidirectional"))
    )
    (net (code "60") (name "unconnected-(TEENSY-D5{slash}INT{slash}20MA-Pad48)") (class "Default")
      (node (ref "TEENSY") (pin "48") (pinfunction "D5/INT/20MA_48") (pintype "bidirectional"))
    )
    (net (code "61") (name "unconnected-(TEENSY-D6{slash}INT{slash}PWM-Pad45)") (class "Default")
      (node (ref "TEENSY") (pin "45") (pinfunction "D6/INT/PWM_45") (pintype "bidirectional"))
    )
    (net (code "62") (name "unconnected-(TEENSY-D14{slash}A0{slash}INT-Pad42)") (class "Default")
      (node (ref "TEENSY") (pin "42") (pinfunction "D14/A0/INT_42") (pintype "bidirectional"))
    )
    (net (code "63") (name "unconnected-(TEENSY-D16{slash}A2{slash}TOUCH{slash}20MA-Pad27)") (class "Default")
      (node (ref "TEENSY") (pin "27") (pinfunction "D16/A2/TOUCH/20MA_27") (pintype "bidirectional"))
    )
    (net (code "64") (name "unconnected-(TEENSY-D17{slash}A3{slash}TOUCH{slash}PWM{slash}20MA-Pad28)") (class "Default")
      (node (ref "TEENSY") (pin "28") (pinfunction "D17/A3/TOUCH/PWM/20MA_28") (pintype "bidirectional"))
    )
    (net (code "65") (name "unconnected-(TEENSY-D20{slash}A6{slash}SCK1{slash}PWM-Pad46)") (class "Default")
      (node (ref "TEENSY") (pin "46") (pinfunction "D20/A6/SCK1/PWM_46") (pintype "bidirectional"))
    )
    (net (code "66") (name "unconnected-(TEENSY-D21{slash}A7{slash}20MA-Pad47)") (class "Default")
      (node (ref "TEENSY") (pin "47") (pinfunction "D21/A7/20MA_47") (pintype "bidirectional"))
    )
    (net (code "67") (name "unconnected-(TEENSY-D23{slash}A9{slash}SDA1{slash}TOUCH{slash}PWM-Pad35)") (class "Default")
      (node (ref "TEENSY") (pin "35") (pinfunction "D23/A9/SDA1/TOUCH/PWM_35") (pintype "bidirectional"))
    )
    (net (code "68") (name "unconnected-(TEENSY-D24{slash}A10-Pad7)") (class "Default")
      (node (ref "TEENSY") (pin "7") (pinfunction "D24/A10_7") (pintype "bidirectional"))
    )
    (net (code "69") (name "unconnected-(TEENSY-D25{slash}A11-Pad8)") (class "Default")
      (node (ref "TEENSY") (pin "8") (pinfunction "D25/A11_8") (pintype "bidirectional"))
    )
    (net (code "70") (name "unconnected-(TEENSY-NMI-B-Pad21)") (class "Default")
      (node (ref "TEENSY") (pin "21") (pinfunction "NMI-B_21") (pintype "bidirectional"))
    )
    (net (code "71") (name "unconnected-(TEENSY-PTE24-Pad15)") (class "Default")
      (node (ref "TEENSY") (pin "15") (pinfunction "PTE24_15") (pintype "bidirectional"))
    )
    (net (code "72") (name "unconnected-(TEENSY-PTE25-Pad16)") (class "Default")
      (node (ref "TEENSY") (pin "16") (pinfunction "PTE25_16") (pintype "bidirectional"))
    )
    (net (code "73") (name "unconnected-(TEENSY-PTE29-Pad13)") (class "Default")
      (node (ref "TEENSY") (pin "13") (pinfunction "PTE29_13") (pintype "bidirectional"))
    )
    (net (code "74") (name "unconnected-(TEENSY-VREF-H-Pad10)") (class "Default")
      (node (ref "TEENSY") (pin "10") (pinfunction "VREF-H_10") (pintype "bidirectional"))
    )
    (net (code "75") (name "unconnected-(U$8-ID-PadP$4)") (class "Default")
      (node (ref "U$8") (pin "P$4") (pinfunction "ID_P$4") (pintype "bidirectional"))
    )
  )
)
